# micro_opto_v1_2.net
KiCad netlist of a schematic drawn in EAGLE
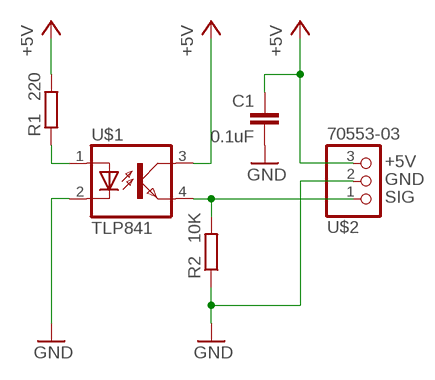
[diagram p0: schematic, sheet 1]

(export (version "E")
  (design (tool "Eeschema 10.0.6"))
  (components
    (comp (ref "C1")
      (value "0.1uF")
      (footprint "eagle-import:C0805")
      (libsource (lib "eagle-import") (part "C-EUC0805"))
    )
    (comp (ref "R1")
      (value "220")
      (footprint "eagle-import:R0805")
      (libsource (lib "eagle-import") (part "R-EU_R0805"))
    )
    (comp (ref "R2")
      (value "10K")
      (footprint "eagle-import:R0805")
      (libsource (lib "eagle-import") (part "R-EU_R0805"))
    )
    (comp (ref "U$1")
      (value "TLP841")
      (footprint "eagle-import:TLP841")
      (libsource (lib "eagle-import") (part "TLP841"))
    )
    (comp (ref "U$2")
      (value "70553-03")
      (footprint "eagle-import:70553-03")
      (libsource (lib "eagle-import") (part "70553-03"))
    )
  )
  (nets
    (net (code "1") (name "+5V") (class "Default")
      (node (ref "C1") (pin "1") (pinfunction "1_1") (pintype "passive"))
      (node (ref "R1") (pin "2") (pinfunction "2_2") (pintype "passive"))
      (node (ref "U$1") (pin "3") (pinfunction "COL_3") (pintype "passive"))
      (node (ref "U$2") (pin "3") (pinfunction "3_3") (pintype "passive"))
    )
    (net (code "2") (name "GND") (class "Default")
      (node (ref "C1") (pin "2") (pinfunction "2_2") (pintype "passive"))
      (node (ref "R2") (pin "1") (pinfunction "1_1") (pintype "passive"))
      (node (ref "U$1") (pin "2") (pinfunction "C_2") (pintype "passive"))
      (node (ref "U$2") (pin "2") (pinfunction "2_2") (pintype "passive"))
    )
    (net (code "3") (name "Net-(U$1-A)") (class "Default")
      (node (ref "R1") (pin "1") (pinfunction "1_1") (pintype "passive"))
      (node (ref "U$1") (pin "1") (pinfunction "A_1") (pintype "passive"))
    )
    (net (code "4") (name "Net-(U$1-EMIT)") (class "Default")
      (node (ref "R2") (pin "2") (pinfunction "2_2") (pintype "passive"))
      (node (ref "U$1") (pin "4") (pinfunction "EMIT_4") (pintype "passive"))
      (node (ref "U$2") (pin "1") (pinfunction "1_1") (pintype "passive"))
    )
  )
)
